# STM32F405.net
KiCad netlist of a schematic drawn in Altium Designer
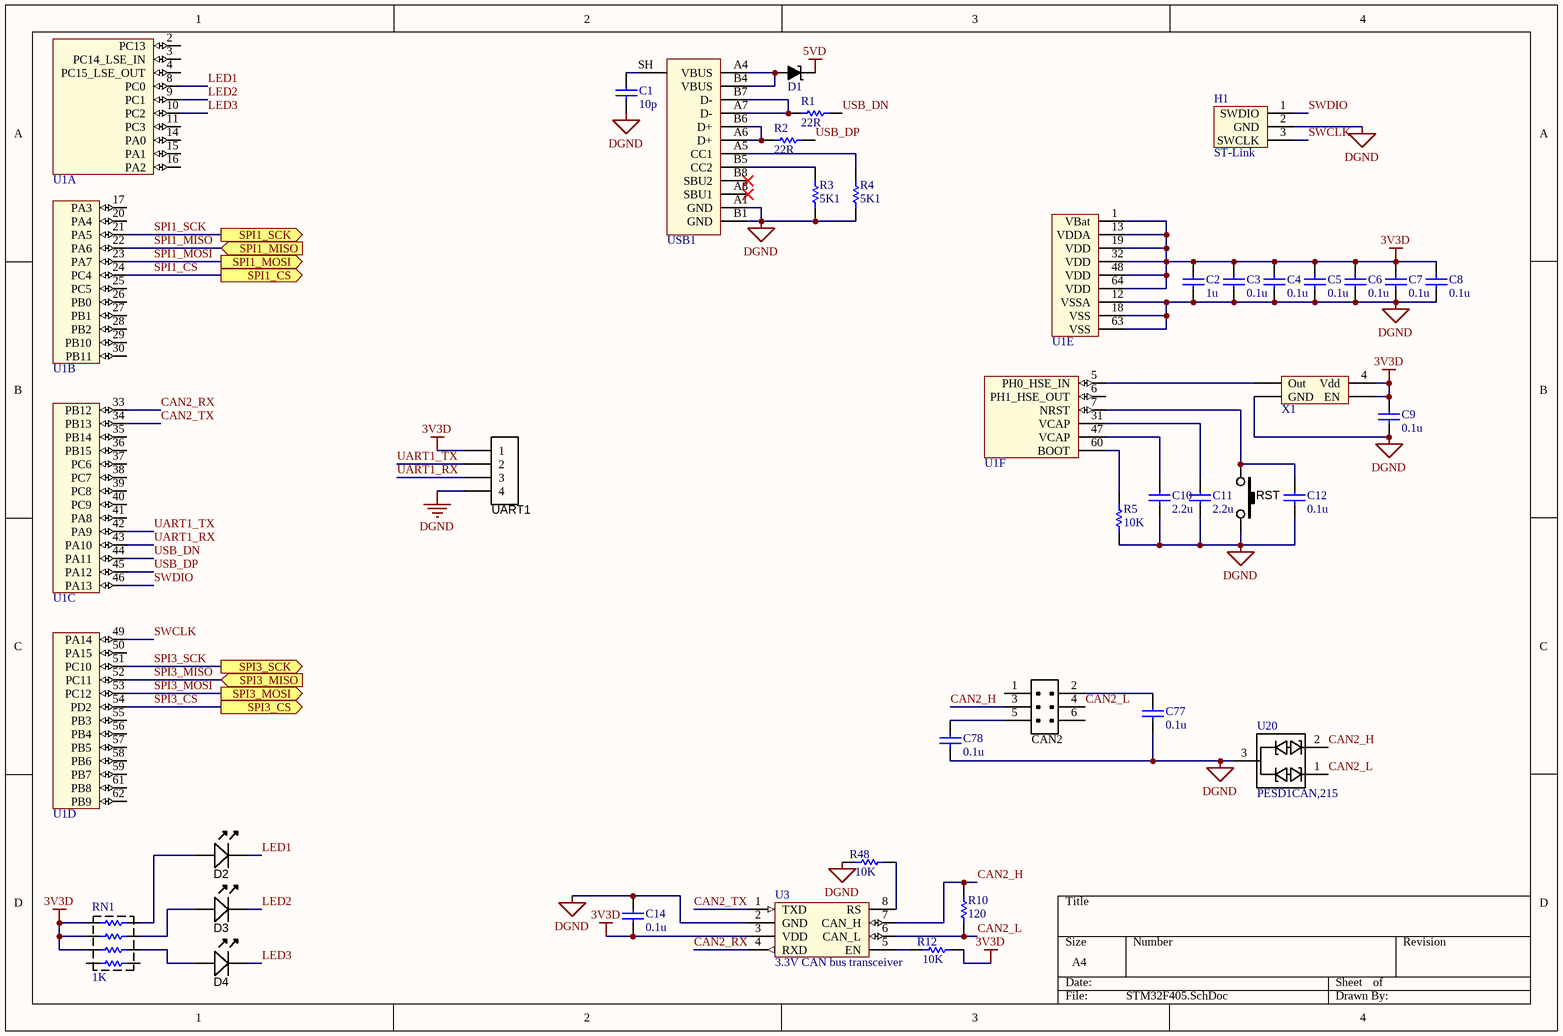
[diagram p0: STM32F405.SchDoc]

(export (version "E")
  (design (tool "Eeschema 10.0.6"))
  (components
    (comp (ref "C1")
      (value "10p")
      (footprint "CAPC1608X90N")
      (description "Capacitor")
      (fields (field (name "Comment") "Cap") (field (name "PUBLISHER") "Altium Limited"))
      (libsource (lib "IOBoard_Low") (part "Cap"))
    )
    (comp (ref "C2")
      (value "1u")
      (footprint "CAPC1608X90N")
      (description "Capacitor")
      (fields (field (name "Comment") "Cap") (field (name "PUBLISHER") "Altium Limited"))
      (libsource (lib "IOBoard_Low") (part "Cap"))
    )
    (comp (ref "C3")
      (value "0.1u")
      (footprint "CAPC1608X90N")
      (description "Capacitor")
      (fields (field (name "Comment") "Cap") (field (name "PUBLISHER") "Altium Limited"))
      (libsource (lib "IOBoard_Low") (part "Cap"))
    )
    (comp (ref "C4")
      (value "0.1u")
      (footprint "CAPC1608X90N")
      (description "Capacitor")
      (fields (field (name "Comment") "Cap") (field (name "PUBLISHER") "Altium Limited"))
      (libsource (lib "IOBoard_Low") (part "Cap"))
    )
    (comp (ref "C5")
      (value "0.1u")
      (footprint "CAPC1608X90N")
      (description "Capacitor")
      (fields (field (name "Comment") "Cap") (field (name "PUBLISHER") "Altium Limited"))
      (libsource (lib "IOBoard_Low") (part "Cap"))
    )
    (comp (ref "C6")
      (value "0.1u")
      (footprint "CAPC1608X90N")
      (description "Capacitor")
      (fields (field (name "Comment") "Cap") (field (name "PUBLISHER") "Altium Limited"))
      (libsource (lib "IOBoard_Low") (part "Cap"))
    )
    (comp (ref "C7")
      (value "0.1u")
      (footprint "CAPC1608X90N")
      (description "Capacitor")
      (fields (field (name "Comment") "Cap") (field (name "PUBLISHER") "Altium Limited"))
      (libsource (lib "IOBoard_Low") (part "Cap"))
    )
    (comp (ref "C8")
      (value "0.1u")
      (footprint "CAPC1608X90N")
      (description "Capacitor")
      (fields (field (name "Comment") "Cap") (field (name "PUBLISHER") "Altium Limited"))
      (libsource (lib "IOBoard_Low") (part "Cap"))
    )
    (comp (ref "C9")
      (value "0.1u")
      (footprint "CAPC1608X90N")
      (description "Capacitor")
      (fields (field (name "Comment") "Cap") (field (name "PUBLISHER") "Altium Limited"))
      (libsource (lib "IOBoard_Low") (part "Cap"))
    )
    (comp (ref "C10")
      (value "2.2u")
      (footprint "CAPC1608X90N")
      (description "Capacitor")
      (fields (field (name "Comment") "Cap") (field (name "PUBLISHER") "Altium Limited"))
      (libsource (lib "IOBoard_Low") (part "Cap"))
    )
    (comp (ref "C11")
      (value "2.2u")
      (footprint "CAPC1608X90N")
      (description "Capacitor")
      (fields (field (name "Comment") "Cap") (field (name "PUBLISHER") "Altium Limited"))
      (libsource (lib "IOBoard_Low") (part "Cap"))
    )
    (comp (ref "C12")
      (value "0.1u")
      (footprint "CAPC1608X90N")
      (description "Capacitor")
      (fields (field (name "Comment") "Cap") (field (name "PUBLISHER") "Altium Limited"))
      (libsource (lib "IOBoard_Low") (part "Cap"))
    )
    (comp (ref "C14")
      (value "0.1u")
      (footprint "CAPC1608X90N")
      (description "Capacitor")
      (fields (field (name "Comment") "Cap") (field (name "PUBLISHER") "Altium Limited"))
      (libsource (lib "IOBoard_Low") (part "Cap"))
    )
    (comp (ref "C77")
      (value "0.1u")
      (footprint "CAPC1608X90N")
      (description "Capacitor")
      (fields (field (name "Comment") "Cap") (field (name "PUBLISHER") "Altium Limited"))
      (libsource (lib "IOBoard_Low") (part "Cap"))
    )
    (comp (ref "C78")
      (value "0.1u")
      (footprint "CAPC1608X90N")
      (description "Capacitor")
      (fields (field (name "Comment") "Cap") (field (name "PUBLISHER") "Altium Limited"))
      (libsource (lib "IOBoard_Low") (part "Cap"))
    )
    (comp (ref "CAN2")
      (value "Header, 2x3-pin")
      (footprint "HDR2X3_2.54MMP_RA")
      (libsource (lib "IOBoard") (part "Header_2x3P"))
    )
    (comp (ref "D1")
      (value "diode")
      (footprint "DIODE_3216_70N")
      (description "40V 2A")
      (libsource (lib "IOBoard_Low") (part "SD1206S040S2R0"))
    )
    (comp (ref "D2")
      (value "LED_Green_GullWing")
      (footprint "LED-0805-A")
      (description "LED Gull-wing SMD High-intensity Green 450mcd 574nm")
      (libsource (lib "IOBoard") (part "LED_Green_GullWing"))
    )
    (comp (ref "D3")
      (value "LED_Green_GullWing")
      (footprint "LED-0805-A")
      (description "LED Gull-wing SMD High-intensity Green 450mcd 574nm")
      (libsource (lib "IOBoard") (part "LED_Green_GullWing"))
    )
    (comp (ref "D4")
      (value "LED_Green_GullWing")
      (footprint "LED-0805-A")
      (description "LED Gull-wing SMD High-intensity Green 450mcd 574nm")
      (libsource (lib "IOBoard") (part "LED_Green_GullWing"))
    )
    (comp (ref "H1")
      (value "ST-Link")
      (footprint "ST-Link")
      (description "ST-Link header with silkscreen")
      (libsource (lib "IOBoard") (part "ST-Link"))
    )
    (comp (ref "R1")
      (value "22R")
      (footprint "RESC1608X55N")
      (description "Resistor")
      (fields (field (name "Comment") "Res1") (field (name "PUBLISHER") "Altium Limited"))
      (libsource (lib "IOBoard_Low") (part "Res1"))
    )
    (comp (ref "R2")
      (value "22R")
      (footprint "RESC1608X55N")
      (description "Resistor")
      (fields (field (name "Comment") "Res1") (field (name "PUBLISHER") "Altium Limited"))
      (libsource (lib "IOBoard_Low") (part "Res1"))
    )
    (comp (ref "R3")
      (value "5K1")
      (footprint "RESC1608X55N")
      (description "Resistor")
      (fields (field (name "Comment") "Res1") (field (name "PUBLISHER") "Altium Limited"))
      (libsource (lib "IOBoard_Low") (part "Res1"))
    )
    (comp (ref "R4")
      (value "5K1")
      (footprint "RESC1608X55N")
      (description "Resistor")
      (fields (field (name "Comment") "Res1") (field (name "PUBLISHER") "Altium Limited"))
      (libsource (lib "IOBoard_Low") (part "Res1"))
    )
    (comp (ref "R5")
      (value "10K")
      (footprint "RESC1608X55N")
      (description "Resistor")
      (fields (field (name "Comment") "Res1") (field (name "PUBLISHER") "Altium Limited"))
      (libsource (lib "IOBoard_Low") (part "Res1"))
    )
    (comp (ref "R10")
      (value "120")
      (footprint "RESC1608X55N")
      (description "Resistor")
      (fields (field (name "Comment") "Res1") (field (name "PUBLISHER") "Altium Limited"))
      (libsource (lib "IOBoard_Low") (part "Res1"))
    )
    (comp (ref "R12")
      (value "10K")
      (footprint "RESC1608X55N")
      (description "Resistor")
      (fields (field (name "Comment") "Res1") (field (name "PUBLISHER") "Altium Limited"))
      (libsource (lib "IOBoard_Low") (part "Res1"))
    )
    (comp (ref "R48")
      (value "10K")
      (footprint "RESC1608X55N")
      (description "Resistor")
      (fields (field (name "Comment") "Res1") (field (name "PUBLISHER") "Altium Limited"))
      (libsource (lib "IOBoard_Low") (part "Res1"))
    )
    (comp (ref "RN1")
      (value "1K")
      (footprint "RESCAXS50P160X320X70-8N")
      (fields (field (name "Comment") "resistor network"))
      (libsource (lib "IOBoard") (part "RES_NET"))
    )
    (comp (ref "RST")
      (value "SW_THT_PB_4.3mm")
      (footprint "TACT_SWT-SMD-4.4")
      (description "Switch, tact, 4.3mm stem")
      (libsource (lib "IOBoard") (part "SW_THT_PB_4.3mm"))
    )
    (comp (ref "U1")
      (value "STM32F405RE")
      (footprint "LQFP64")
      (description "STM32F405RE 64 pin package, Cortex M4 core with up to")
      (libsource (lib "IOBoard") (part "STM32F405RE"))
    )
    (comp (ref "U3")
      (value "3.3V CAN bus transceiver")
      (footprint "SOIC127P600X175-8AN")
      (description "3.3V CAN bus transceiver up to 1Mbps")
      (libsource (lib "IOBoard") (part "SN65HVD234-Q1"))
    )
    (comp (ref "U20")
      (value "PESD1CAN,215")
      (footprint "SOT23-3")
      (description "ESD protection for CAN bus. Clamp voltage is 40V")
      (libsource (lib "IOBoard") (part "PESD1CAN,215"))
    )
    (comp (ref "UART1")
      (value "Programmer")
      (footprint "HDR1X4_2.54MMP")
      (description "Header 4-pin")
      (libsource (lib "IOBoard") (part "Header4P"))
    )
    (comp (ref "USB1")
      (value "USB type C connector")
      (footprint "TYPE-C-31-M-12")
      (libsource (lib "IOBoard") (part "USB_Type_C"))
    )
    (comp (ref "X1")
      (value "ASE-8.000MHZ-LC-T")
      (footprint "ASE Series")
      (description "8MHz")
      (libsource (lib "IOBoard") (part "ASE-8.000MHZ-LC-T"))
    )
  )
  (nets
    (net (code "1") (name "/CAN2_H") (class "Default")
      (node (ref "CAN2") (pin "3") (pinfunction "3_3") (pintype "passive"))
      (node (ref "R10") (pin "2") (pinfunction "2_2") (pintype "passive"))
      (node (ref "U20") (pin "2") (pinfunction "2_2") (pintype "power_in"))
      (node (ref "U3") (pin "7") (pinfunction "CAN_H_7") (pintype "bidirectional"))
    )
    (net (code "2") (name "/CAN2_L") (class "Default")
      (node (ref "CAN2") (pin "4") (pinfunction "4_4") (pintype "passive"))
      (node (ref "R10") (pin "1") (pinfunction "1_1") (pintype "passive"))
      (node (ref "U20") (pin "1") (pinfunction "1_1") (pintype "power_in"))
      (node (ref "U3") (pin "6") (pinfunction "CAN_L_6") (pintype "bidirectional"))
    )
    (net (code "3") (name "/CAN2_RX") (class "Default")
      (node (ref "U1") (pin "33") (pinfunction "PB12_33") (pintype "bidirectional"))
      (node (ref "U3") (pin "4") (pinfunction "RXD_4") (pintype "output"))
    )
    (net (code "4") (name "/CAN2_TX") (class "Default")
      (node (ref "U1") (pin "34") (pinfunction "PB13_34") (pintype "bidirectional"))
      (node (ref "U3") (pin "1") (pinfunction "TXD_1") (pintype "input"))
    )
    (net (code "5") (name "/LED1") (class "Default")
      (node (ref "D2") (pin "K") (pinfunction "K_K") (pintype "passive"))
      (node (ref "U1") (pin "8") (pinfunction "PC0_8") (pintype "bidirectional"))
    )
    (net (code "6") (name "/LED2") (class "Default")
      (node (ref "D3") (pin "K") (pinfunction "K_K") (pintype "passive"))
      (node (ref "U1") (pin "9") (pinfunction "PC1_9") (pintype "bidirectional"))
    )
    (net (code "7") (name "/LED3") (class "Default")
      (node (ref "D4") (pin "K") (pinfunction "K_K") (pintype "passive"))
      (node (ref "U1") (pin "10") (pinfunction "PC2_10") (pintype "bidirectional"))
    )
    (net (code "8") (name "/SPI1_CS") (class "Default")
      (node (ref "U1") (pin "24") (pinfunction "PC4_24") (pintype "bidirectional"))
    )
    (net (code "9") (name "/SPI1_MISO") (class "Default")
      (node (ref "U1") (pin "22") (pinfunction "PA6_22") (pintype "bidirectional"))
    )
    (net (code "10") (name "/SPI1_MOSI") (class "Default")
      (node (ref "U1") (pin "23") (pinfunction "PA7_23") (pintype "bidirectional"))
    )
    (net (code "11") (name "/SPI1_SCK") (class "Default")
      (node (ref "U1") (pin "21") (pinfunction "PA5_21") (pintype "bidirectional"))
    )
    (net (code "12") (name "/SPI3_CS") (class "Default")
      (node (ref "U1") (pin "54") (pinfunction "PD2_54") (pintype "bidirectional"))
    )
    (net (code "13") (name "/SPI3_MISO") (class "Default")
      (node (ref "U1") (pin "52") (pinfunction "PC11_52") (pintype "bidirectional"))
    )
    (net (code "14") (name "/SPI3_MOSI") (class "Default")
      (node (ref "U1") (pin "53") (pinfunction "PC12_53") (pintype "bidirectional"))
    )
    (net (code "15") (name "/SPI3_SCK") (class "Default")
      (node (ref "U1") (pin "51") (pinfunction "PC10_51") (pintype "bidirectional"))
    )
    (net (code "16") (name "/SWCLK") (class "Default")
      (node (ref "H1") (pin "3") (pinfunction "SWCLK_3") (pintype "power_in"))
      (node (ref "U1") (pin "49") (pinfunction "PA14_49") (pintype "bidirectional"))
    )
    (net (code "17") (name "/SWDIO") (class "Default")
      (node (ref "H1") (pin "1") (pinfunction "SWDIO_1") (pintype "power_in"))
      (node (ref "U1") (pin "46") (pinfunction "PA13_46") (pintype "bidirectional"))
    )
    (net (code "18") (name "/UART1_RX") (class "Default")
      (node (ref "U1") (pin "43") (pinfunction "PA10_43") (pintype "bidirectional"))
      (node (ref "UART1") (pin "3") (pinfunction "3_3") (pintype "passive"))
    )
    (net (code "19") (name "/UART1_TX") (class "Default")
      (node (ref "U1") (pin "42") (pinfunction "PA9_42") (pintype "bidirectional"))
      (node (ref "UART1") (pin "2") (pinfunction "2_2") (pintype "passive"))
    )
    (net (code "20") (name "/USB_DN") (class "Default")
      (node (ref "R1") (pin "2") (pinfunction "2_2") (pintype "passive"))
      (node (ref "U1") (pin "44") (pinfunction "PA11_44") (pintype "bidirectional"))
    )
    (net (code "21") (name "/USB_DP") (class "Default")
      (node (ref "R2") (pin "2") (pinfunction "2_2") (pintype "passive"))
      (node (ref "U1") (pin "45") (pinfunction "PA12_45") (pintype "bidirectional"))
    )
    (net (code "22") (name "3V3D") (class "Default")
      (node (ref "C14") (pin "1") (pinfunction "1_1") (pintype "passive"))
      (node (ref "C2") (pin "2") (pinfunction "2_2") (pintype "passive"))
      (node (ref "C3") (pin "2") (pinfunction "2_2") (pintype "passive"))
      (node (ref "C4") (pin "2") (pinfunction "2_2") (pintype "passive"))
      (node (ref "C5") (pin "2") (pinfunction "2_2") (pintype "passive"))
      (node (ref "C6") (pin "2") (pinfunction "2_2") (pintype "passive"))
      (node (ref "C7") (pin "2") (pinfunction "2_2") (pintype "passive"))
      (node (ref "C8") (pin "2") (pinfunction "2_2") (pintype "passive"))
      (node (ref "C9") (pin "2") (pinfunction "2_2") (pintype "passive"))
      (node (ref "R12") (pin "1") (pinfunction "1_1") (pintype "passive"))
      (node (ref "RN1") (pin "1") (pinfunction "1_1") (pintype "power_in"))
      (node (ref "RN1") (pin "2") (pinfunction "2_2") (pintype "power_in"))
      (node (ref "RN1") (pin "3") (pinfunction "3_3") (pintype "power_in"))
      (node (ref "U1") (pin "1") (pinfunction "VBat_1") (pintype "power_in"))
      (node (ref "U1") (pin "13") (pinfunction "VDDA_13") (pintype "power_in"))
      (node (ref "U1") (pin "19") (pinfunction "VDD_19") (pintype "power_in"))
      (node (ref "U1") (pin "32") (pinfunction "VDD_32") (pintype "power_in"))
      (node (ref "U1") (pin "48") (pinfunction "VDD_48") (pintype "power_in"))
      (node (ref "U1") (pin "64") (pinfunction "VDD_64") (pintype "power_in"))
      (node (ref "U3") (pin "3") (pinfunction "VDD_3") (pintype "power_in"))
      (node (ref "UART1") (pin "1") (pinfunction "1_1") (pintype "passive"))
      (node (ref "X1") (pin "1") (pinfunction "EN_1") (pintype "passive"))
      (node (ref "X1") (pin "4") (pinfunction "Vdd_4") (pintype "passive"))
    )
    (net (code "23") (name "5VD") (class "Default")
      (node (ref "D1") (pin "K") (pinfunction "Cathode_K") (pintype "passive"))
    )
    (net (code "24") (name "DGND") (class "Default")
      (node (ref "C1") (pin "1") (pinfunction "1_1") (pintype "passive"))
      (node (ref "C10") (pin "1") (pinfunction "1_1") (pintype "passive"))
      (node (ref "C11") (pin "1") (pinfunction "1_1") (pintype "passive"))
      (node (ref "C12") (pin "1") (pinfunction "1_1") (pintype "passive"))
      (node (ref "C14") (pin "2") (pinfunction "2_2") (pintype "passive"))
      (node (ref "C2") (pin "1") (pinfunction "1_1") (pintype "passive"))
      (node (ref "C3") (pin "1") (pinfunction "1_1") (pintype "passive"))
      (node (ref "C4") (pin "1") (pinfunction "1_1") (pintype "passive"))
      (node (ref "C5") (pin "1") (pinfunction "1_1") (pintype "passive"))
      (node (ref "C6") (pin "1") (pinfunction "1_1") (pintype "passive"))
      (node (ref "C7") (pin "1") (pinfunction "1_1") (pintype "passive"))
      (node (ref "C77") (pin "2") (pinfunction "2_2") (pintype "passive"))
      (node (ref "C78") (pin "1") (pinfunction "1_1") (pintype "passive"))
      (node (ref "C8") (pin "1") (pinfunction "1_1") (pintype "passive"))
      (node (ref "C9") (pin "1") (pinfunction "1_1") (pintype "passive"))
      (node (ref "H1") (pin "2") (pinfunction "GND_2") (pintype "power_in"))
      (node (ref "R3") (pin "1") (pinfunction "1_1") (pintype "passive"))
      (node (ref "R4") (pin "1") (pinfunction "1_1") (pintype "passive"))
      (node (ref "R48") (pin "2") (pinfunction "2_2") (pintype "passive"))
      (node (ref "R5") (pin "1") (pinfunction "1_1") (pintype "passive"))
      (node (ref "RST") (pin "2") (pintype "passive"))
      (node (ref "U1") (pin "12") (pinfunction "VSSA_12") (pintype "power_in"))
      (node (ref "U1") (pin "18") (pinfunction "VSS_18") (pintype "power_in"))
      (node (ref "U1") (pin "63") (pinfunction "VSS_63") (pintype "power_in"))
      (node (ref "U20") (pin "3") (pinfunction "3_3") (pintype "power_in"))
      (node (ref "U3") (pin "2") (pinfunction "GND_2") (pintype "power_in"))
      (node (ref "UART1") (pin "4") (pinfunction "4_4") (pintype "passive"))
      (node (ref "USB1") (pin "A1") (pinfunction "GND_A1") (pintype "power_in"))
      (node (ref "USB1") (pin "B1") (pinfunction "GND_B1") (pintype "power_in"))
      (node (ref "X1") (pin "2") (pinfunction "GND_2") (pintype "passive"))
    )
    (net (code "25") (name "Net-(C1-Pad2)") (class "Default")
      (node (ref "C1") (pin "2") (pinfunction "2_2") (pintype "passive"))
      (node (ref "USB1") (pin "SH") (pinfunction "SH_SH") (pintype "power_in"))
    )
    (net (code "26") (name "Net-(C10-Pad2)") (class "Default")
      (node (ref "C10") (pin "2") (pinfunction "2_2") (pintype "passive"))
      (node (ref "U1") (pin "47") (pinfunction "VCAP_47") (pintype "power_in"))
    )
    (net (code "27") (name "Net-(C11-Pad2)") (class "Default")
      (node (ref "C11") (pin "2") (pinfunction "2_2") (pintype "passive"))
      (node (ref "U1") (pin "31") (pinfunction "VCAP_31") (pintype "power_in"))
    )
    (net (code "28") (name "Net-(C77-Pad1)") (class "Default")
      (node (ref "C77") (pin "1") (pinfunction "1_1") (pintype "passive"))
      (node (ref "CAN2") (pin "2") (pinfunction "2_2") (pintype "passive"))
    )
    (net (code "29") (name "Net-(C78-Pad2)") (class "Default")
      (node (ref "C78") (pin "2") (pinfunction "2_2") (pintype "passive"))
      (node (ref "CAN2") (pin "5") (pinfunction "5_5") (pintype "passive"))
    )
    (net (code "30") (name "Net-(D1-Anode)") (class "Default")
      (node (ref "D1") (pin "A") (pinfunction "Anode_A") (pintype "passive"))
      (node (ref "USB1") (pin "A4") (pinfunction "VBUS_A4") (pintype "power_in"))
      (node (ref "USB1") (pin "B4") (pinfunction "VBUS_B4") (pintype "power_in"))
    )
    (net (code "31") (name "Net-(D2-PadA)") (class "Default")
      (node (ref "D2") (pin "A") (pinfunction "A_A") (pintype "passive"))
      (node (ref "RN1") (pin "8") (pinfunction "8_8") (pintype "passive"))
    )
    (net (code "32") (name "Net-(D3-PadA)") (class "Default")
      (node (ref "D3") (pin "A") (pinfunction "A_A") (pintype "passive"))
      (node (ref "RN1") (pin "7") (pinfunction "7_7") (pintype "power_in"))
    )
    (net (code "33") (name "Net-(D4-PadA)") (class "Default")
      (node (ref "D4") (pin "A") (pinfunction "A_A") (pintype "passive"))
      (node (ref "RN1") (pin "6") (pinfunction "6_6") (pintype "power_in"))
    )
    (net (code "34") (name "Net-(R1-Pad1)") (class "Default")
      (node (ref "R1") (pin "1") (pinfunction "1_1") (pintype "passive"))
      (node (ref "USB1") (pin "A7") (pinfunction "D-_A7") (pintype "power_in"))
      (node (ref "USB1") (pin "B7") (pinfunction "D-_B7") (pintype "power_in"))
    )
    (net (code "35") (name "Net-(R2-Pad1)") (class "Default")
      (node (ref "R2") (pin "1") (pinfunction "1_1") (pintype "passive"))
      (node (ref "USB1") (pin "A6") (pinfunction "D+_A6") (pintype "power_in"))
      (node (ref "USB1") (pin "B6") (pinfunction "D+_B6") (pintype "power_in"))
    )
    (net (code "36") (name "Net-(U1F-BOOT)") (class "Default")
      (node (ref "R5") (pin "2") (pinfunction "2_2") (pintype "passive"))
      (node (ref "U1") (pin "60") (pinfunction "BOOT_60") (pintype "passive"))
    )
    (net (code "37") (name "Net-(U1F-NRST)") (class "Default")
      (node (ref "C12") (pin "2") (pinfunction "2_2") (pintype "passive"))
      (node (ref "RST") (pin "1") (pintype "passive"))
      (node (ref "U1") (pin "7") (pinfunction "NRST_7") (pintype "bidirectional"))
    )
    (net (code "38") (name "Net-(U1F-PH0_HSE_IN)") (class "Default")
      (node (ref "U1") (pin "5") (pinfunction "PH0_HSE_IN_5") (pintype "bidirectional"))
      (node (ref "X1") (pin "3") (pinfunction "Out_3") (pintype "passive"))
    )
    (net (code "39") (name "Net-(U3-EN)") (class "Default")
      (node (ref "R12") (pin "2") (pinfunction "2_2") (pintype "passive"))
      (node (ref "U3") (pin "5") (pinfunction "EN_5") (pintype "passive"))
    )
    (net (code "40") (name "Net-(U3-RS)") (class "Default")
      (node (ref "R48") (pin "1") (pinfunction "1_1") (pintype "passive"))
      (node (ref "U3") (pin "8") (pinfunction "RS_8") (pintype "passive"))
    )
    (net (code "41") (name "Net-(USB1-CC1)") (class "Default")
      (node (ref "R4") (pin "2") (pinfunction "2_2") (pintype "passive"))
      (node (ref "USB1") (pin "A5") (pinfunction "CC1_A5") (pintype "power_in"))
    )
    (net (code "42") (name "Net-(USB1-CC2)") (class "Default")
      (node (ref "R3") (pin "2") (pinfunction "2_2") (pintype "passive"))
      (node (ref "USB1") (pin "B5") (pinfunction "CC2_B5") (pintype "power_in"))
    )
    (net (code "43") (name "unconnected-(CAN2-Pad1)") (class "Default")
      (node (ref "CAN2") (pin "1") (pinfunction "1_1") (pintype "passive"))
    )
    (net (code "44") (name "unconnected-(CAN2-Pad6)") (class "Default")
      (node (ref "CAN2") (pin "6") (pinfunction "6_6") (pintype "passive"))
    )
    (net (code "45") (name "unconnected-(RN1-Pad4)") (class "Default")
      (node (ref "RN1") (pin "4") (pinfunction "4_4") (pintype "power_in"))
    )
    (net (code "46") (name "unconnected-(RN1-Pad5)") (class "Default")
      (node (ref "RN1") (pin "5") (pinfunction "5_5") (pintype "power_in"))
    )
    (net (code "47") (name "unconnected-(U1A-PA0-Pad14)") (class "Default")
      (node (ref "U1") (pin "14") (pinfunction "PA0_14") (pintype "bidirectional"))
    )
    (net (code "48") (name "unconnected-(U1A-PA1-Pad15)") (class "Default")
      (node (ref "U1") (pin "15") (pinfunction "PA1_15") (pintype "bidirectional"))
    )
    (net (code "49") (name "unconnected-(U1A-PA2-Pad16)") (class "Default")
      (node (ref "U1") (pin "16") (pinfunction "PA2_16") (pintype "bidirectional"))
    )
    (net (code "50") (name "unconnected-(U1A-PC3-Pad11)") (class "Default")
      (node (ref "U1") (pin "11") (pinfunction "PC3_11") (pintype "bidirectional"))
    )
    (net (code "51") (name "unconnected-(U1A-PC13-Pad2)") (class "Default")
      (node (ref "U1") (pin "2") (pinfunction "PC13_2") (pintype "bidirectional"))
    )
    (net (code "52") (name "unconnected-(U1A-PC14_LSE_IN-Pad3)") (class "Default")
      (node (ref "U1") (pin "3") (pinfunction "PC14_LSE_IN_3") (pintype "bidirectional"))
    )
    (net (code "53") (name "unconnected-(U1A-PC15_LSE_OUT-Pad4)") (class "Default")
      (node (ref "U1") (pin "4") (pinfunction "PC15_LSE_OUT_4") (pintype "bidirectional"))
    )
    (net (code "54") (name "unconnected-(U1B-PA3-Pad17)") (class "Default")
      (node (ref "U1") (pin "17") (pinfunction "PA3_17") (pintype "bidirectional"))
    )
    (net (code "55") (name "unconnected-(U1B-PA4-Pad20)") (class "Default")
      (node (ref "U1") (pin "20") (pinfunction "PA4_20") (pintype "bidirectional"))
    )
    (net (code "56") (name "unconnected-(U1B-PB0-Pad26)") (class "Default")
      (node (ref "U1") (pin "26") (pinfunction "PB0_26") (pintype "bidirectional"))
    )
    (net (code "57") (name "unconnected-(U1B-PB1-Pad27)") (class "Default")
      (node (ref "U1") (pin "27") (pinfunction "PB1_27") (pintype "bidirectional"))
    )
    (net (code "58") (name "unconnected-(U1B-PB2-Pad28)") (class "Default")
      (node (ref "U1") (pin "28") (pinfunction "PB2_28") (pintype "bidirectional"))
    )
    (net (code "59") (name "unconnected-(U1B-PB10-Pad29)") (class "Default")
      (node (ref "U1") (pin "29") (pinfunction "PB10_29") (pintype "bidirectional"))
    )
    (net (code "60") (name "unconnected-(U1B-PB11-Pad30)") (class "Default")
      (node (ref "U1") (pin "30") (pinfunction "PB11_30") (pintype "bidirectional"))
    )
    (net (code "61") (name "unconnected-(U1B-PC5-Pad25)") (class "Default")
      (node (ref "U1") (pin "25") (pinfunction "PC5_25") (pintype "bidirectional"))
    )
    (net (code "62") (name "unconnected-(U1C-PA8-Pad41)") (class "Default")
      (node (ref "U1") (pin "41") (pinfunction "PA8_41") (pintype "bidirectional"))
    )
    (net (code "63") (name "unconnected-(U1C-PB14-Pad35)") (class "Default")
      (node (ref "U1") (pin "35") (pinfunction "PB14_35") (pintype "bidirectional"))
    )
    (net (code "64") (name "unconnected-(U1C-PB15-Pad36)") (class "Default")
      (node (ref "U1") (pin "36") (pinfunction "PB15_36") (pintype "bidirectional"))
    )
    (net (code "65") (name "unconnected-(U1C-PC6-Pad37)") (class "Default")
      (node (ref "U1") (pin "37") (pinfunction "PC6_37") (pintype "bidirectional"))
    )
    (net (code "66") (name "unconnected-(U1C-PC7-Pad38)") (class "Default")
      (node (ref "U1") (pin "38") (pinfunction "PC7_38") (pintype "bidirectional"))
    )
    (net (code "67") (name "unconnected-(U1C-PC8-Pad39)") (class "Default")
      (node (ref "U1") (pin "39") (pinfunction "PC8_39") (pintype "bidirectional"))
    )
    (net (code "68") (name "unconnected-(U1C-PC9-Pad40)") (class "Default")
      (node (ref "U1") (pin "40") (pinfunction "PC9_40") (pintype "bidirectional"))
    )
    (net (code "69") (name "unconnected-(U1D-PA15-Pad50)") (class "Default")
      (node (ref "U1") (pin "50") (pinfunction "PA15_50") (pintype "bidirectional"))
    )
    (net (code "70") (name "unconnected-(U1D-PB3-Pad55)") (class "Default")
      (node (ref "U1") (pin "55") (pinfunction "PB3_55") (pintype "bidirectional"))
    )
    (net (code "71") (name "unconnected-(U1D-PB4-Pad56)") (class "Default")
      (node (ref "U1") (pin "56") (pinfunction "PB4_56") (pintype "bidirectional"))
    )
    (net (code "72") (name "unconnected-(U1D-PB5-Pad57)") (class "Default")
      (node (ref "U1") (pin "57") (pinfunction "PB5_57") (pintype "bidirectional"))
    )
    (net (code "73") (name "unconnected-(U1D-PB6-Pad58)") (class "Default")
      (node (ref "U1") (pin "58") (pinfunction "PB6_58") (pintype "bidirectional"))
    )
    (net (code "74") (name "unconnected-(U1D-PB7-Pad59)") (class "Default")
      (node (ref "U1") (pin "59") (pinfunction "PB7_59") (pintype "bidirectional"))
    )
    (net (code "75") (name "unconnected-(U1D-PB8-Pad61)") (class "Default")
      (node (ref "U1") (pin "61") (pinfunction "PB8_61") (pintype "bidirectional"))
    )
    (net (code "76") (name "unconnected-(U1D-PB9-Pad62)") (class "Default")
      (node (ref "U1") (pin "62") (pinfunction "PB9_62") (pintype "bidirectional"))
    )
    (net (code "77") (name "unconnected-(U1F-PH1_HSE_OUT-Pad6)") (class "Default")
      (node (ref "U1") (pin "6") (pinfunction "PH1_HSE_OUT_6") (pintype "bidirectional"))
    )
    (net (code "78") (name "unconnected-(USB1-SBU1-PadA8)") (class "Default")
      (node (ref "USB1") (pin "A8") (pinfunction "SBU1_A8") (pintype "power_in+no_connect"))
    )
    (net (code "79") (name "unconnected-(USB1-SBU2-PadB8)") (class "Default")
      (node (ref "USB1") (pin "B8") (pinfunction "SBU2_B8") (pintype "power_in+no_connect"))
    )
  )
)
